# Buck_Converter.net
KiCad netlist of a schematic drawn in Altium Designer
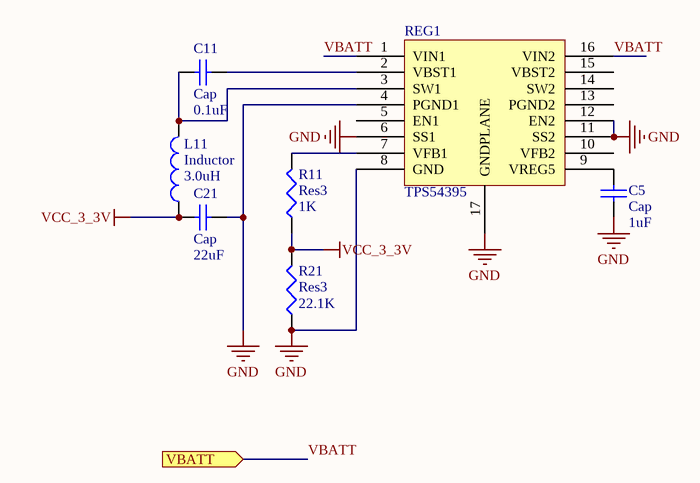
[diagram p0: Buck Converter.SchDoc]

(export (version "E")
  (design (tool "Eeschema 10.0.6"))
  (components
    (comp (ref "C5")
      (value "Cap")
      (footprint "R0805")
      (description "Capacitor")
      (fields (field (name "ALTIUM_VALUE") "1uF") (field (name "PUBLISHER") "Altium Limited"))
      (libsource (lib "Miscellaneous Devices") (part "Cap"))
    )
    (comp (ref "C11")
      (value "Cap")
      (footprint "R0805")
      (description "Capacitor")
      (fields (field (name "ALTIUM_VALUE") "0.1uF") (field (name "PUBLISHER") "Altium Limited"))
      (libsource (lib "Miscellaneous Devices") (part "Cap"))
    )
    (comp (ref "C21")
      (value "Cap")
      (footprint "R0805")
      (description "Capacitor")
      (fields (field (name "ALTIUM_VALUE") "22uF") (field (name "PUBLISHER") "Altium Limited"))
      (libsource (lib "Miscellaneous Devices") (part "Cap"))
    )
    (comp (ref "L11")
      (value "Inductor")
      (footprint "INDUCTOR")
      (fields (field (name "ALTIUM_VALUE") "3.0uH") (field (name "PUBLISHER") "Altium Limited"))
      (libsource (lib "Miscellaneous Devices") (part "Inductor"))
    )
    (comp (ref "R11")
      (value "Res3")
      (footprint "R0805")
      (description "Resistor")
      (fields (field (name "ALTIUM_VALUE") "1K") (field (name "PUBLISHER") "Altium Limited"))
      (libsource (lib "Miscellaneous Devices") (part "Res3"))
    )
    (comp (ref "R21")
      (value "Res3")
      (footprint "R0805")
      (description "Resistor")
      (fields (field (name "ALTIUM_VALUE") "22.1K") (field (name "PUBLISHER") "Altium Limited"))
      (libsource (lib "Miscellaneous Devices") (part "Res3"))
    )
    (comp (ref "REG1")
      (value "TPS54395")
      (footprint "TPS54395")
      (description "Dual Channel Buck Converter")
      (libsource (lib "StrainGaugeLib") (part "TPS54395"))
    )
  )
  (nets
    (net (code "1") (name "/VBATT") (class "Default")
      (node (ref "REG1") (pin "1") (pinfunction "VIN1_1") (pintype "passive"))
      (node (ref "REG1") (pin "16") (pinfunction "VIN2_16") (pintype "passive"))
    )
    (net (code "2") (name "GND") (class "Default")
      (node (ref "C21") (pin "1") (pinfunction "1_1") (pintype "passive"))
      (node (ref "C5") (pin "2") (pinfunction "2_2") (pintype "passive"))
      (node (ref "R21") (pin "1") (pinfunction "1_1") (pintype "passive"))
      (node (ref "REG1") (pin "11") (pinfunction "SS2_11") (pintype "passive"))
      (node (ref "REG1") (pin "12") (pinfunction "EN2_12") (pintype "passive"))
      (node (ref "REG1") (pin "17") (pinfunction "GNDPLANE_17") (pintype "passive"))
      (node (ref "REG1") (pin "4") (pinfunction "PGND1_4") (pintype "passive"))
      (node (ref "REG1") (pin "6") (pinfunction "SS1_6") (pintype "passive"))
      (node (ref "REG1") (pin "8") (pinfunction "GND_8") (pintype "passive"))
    )
    (net (code "3") (name "Net-(REG1-SW1)") (class "Default")
      (node (ref "C11") (pin "2") (pinfunction "2_2") (pintype "passive"))
      (node (ref "L11") (pin "2") (pinfunction "2_2") (pintype "passive"))
      (node (ref "REG1") (pin "3") (pinfunction "SW1_3") (pintype "passive"))
    )
    (net (code "4") (name "Net-(REG1-VBST1)") (class "Default")
      (node (ref "C11") (pin "1") (pinfunction "1_1") (pintype "passive"))
      (node (ref "REG1") (pin "2") (pinfunction "VBST1_2") (pintype "passive"))
    )
    (net (code "5") (name "Net-(REG1-VFB1)") (class "Default")
      (node (ref "R11") (pin "2") (pinfunction "2_2") (pintype "passive"))
      (node (ref "REG1") (pin "7") (pinfunction "VFB1_7") (pintype "passive"))
    )
    (net (code "6") (name "Net-(REG1-VREG5)") (class "Default")
      (node (ref "C5") (pin "1") (pinfunction "1_1") (pintype "passive"))
      (node (ref "REG1") (pin "9") (pinfunction "VREG5_9") (pintype "passive"))
    )
    (net (code "7") (name "VCC_3_3V") (class "Default")
      (node (ref "C21") (pin "2") (pinfunction "2_2") (pintype "passive"))
      (node (ref "L11") (pin "1") (pinfunction "1_1") (pintype "passive"))
      (node (ref "R11") (pin "1") (pinfunction "1_1") (pintype "passive"))
      (node (ref "R21") (pin "2") (pinfunction "2_2") (pintype "passive"))
    )
    (net (code "8") (name "unconnected-(REG1-EN1-Pad5)") (class "Default")
      (node (ref "REG1") (pin "5") (pinfunction "EN1_5") (pintype "passive"))
    )
    (net (code "9") (name "unconnected-(REG1-PGND2-Pad13)") (class "Default")
      (node (ref "REG1") (pin "13") (pinfunction "PGND2_13") (pintype "passive"))
    )
    (net (code "10") (name "unconnected-(REG1-SW2-Pad14)") (class "Default")
      (node (ref "REG1") (pin "14") (pinfunction "SW2_14") (pintype "passive"))
    )
    (net (code "11") (name "unconnected-(REG1-VBST2-Pad15)") (class "Default")
      (node (ref "REG1") (pin "15") (pinfunction "VBST2_15") (pintype "passive"))
    )
    (net (code "12") (name "unconnected-(REG1-VFB2-Pad10)") (class "Default")
      (node (ref "REG1") (pin "10") (pinfunction "VFB2_10") (pintype "passive"))
    )
  )
)
